# ENZANKI.net
KiCad netlist of a schematic drawn in EAGLE
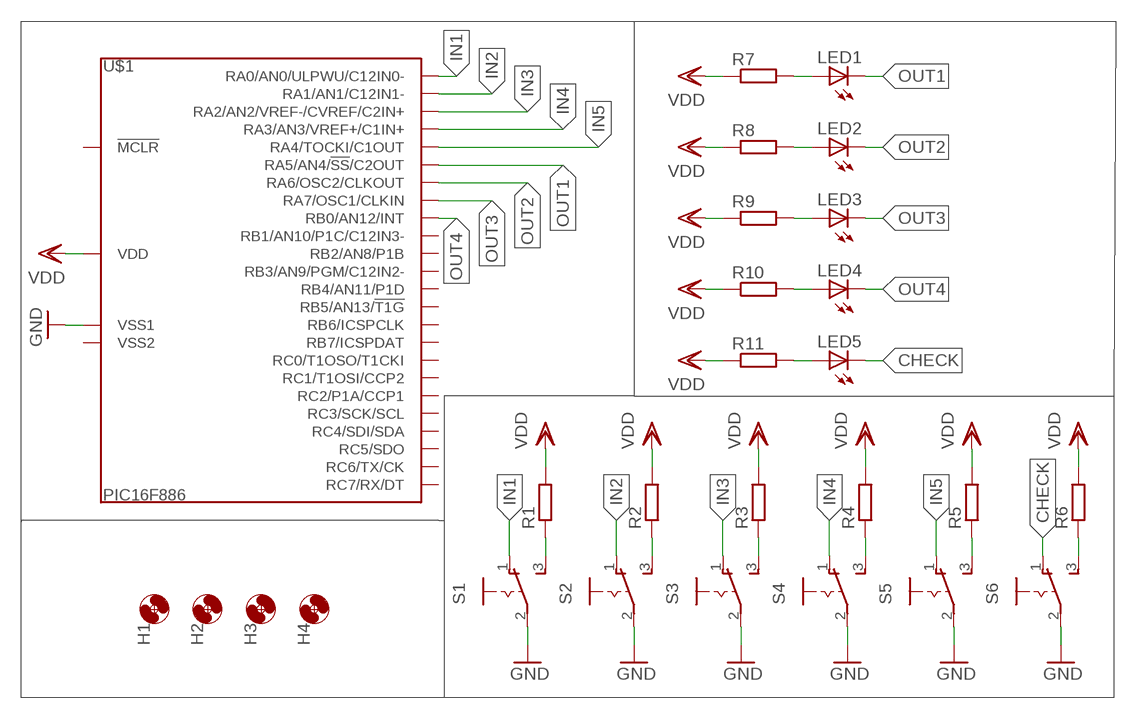
[diagram p0: schematic, sheet 1]

(export (version "E")
  (design (tool "Eeschema 10.0.6"))
  (components
    (comp (ref "H1")
      (value "HOLE3.3M3BOLT")
      (footprint "eagle-import:HOLE3.3")
      (libsource (lib "eagle-import") (part "HOLE3.3M3BOLT"))
    )
    (comp (ref "H2")
      (value "HOLE3.3M3BOLT")
      (footprint "eagle-import:HOLE3.3")
      (libsource (lib "eagle-import") (part "HOLE3.3M3BOLT"))
    )
    (comp (ref "H3")
      (value "HOLE3.3M3BOLT")
      (footprint "eagle-import:HOLE3.3")
      (libsource (lib "eagle-import") (part "HOLE3.3M3BOLT"))
    )
    (comp (ref "H4")
      (value "HOLE3.3M3BOLT")
      (footprint "eagle-import:HOLE3.3")
      (libsource (lib "eagle-import") (part "HOLE3.3M3BOLT"))
    )
    (comp (ref "LED1")
      (value "LED5MM")
      (footprint "eagle-import:LED5MM")
      (libsource (lib "eagle-import") (part "LED5MM"))
    )
    (comp (ref "LED2")
      (value "LED5MM")
      (footprint "eagle-import:LED5MM")
      (libsource (lib "eagle-import") (part "LED5MM"))
    )
    (comp (ref "LED3")
      (value "LED5MM")
      (footprint "eagle-import:LED5MM")
      (libsource (lib "eagle-import") (part "LED5MM"))
    )
    (comp (ref "LED4")
      (value "LED5MM")
      (footprint "eagle-import:LED5MM")
      (libsource (lib "eagle-import") (part "LED5MM"))
    )
    (comp (ref "LED5")
      (value "LED5MM")
      (footprint "eagle-import:LED5MM")
      (libsource (lib "eagle-import") (part "LED5MM"))
    )
    (comp (ref "R1")
      (value "R-EU_R3216W")
      (footprint "eagle-import:R3216W")
      (libsource (lib "eagle-import") (part "R-EU_R3216W"))
    )
    (comp (ref "R2")
      (value "R-EU_R3216W")
      (footprint "eagle-import:R3216W")
      (libsource (lib "eagle-import") (part "R-EU_R3216W"))
    )
    (comp (ref "R3")
      (value "R-EU_R3216W")
      (footprint "eagle-import:R3216W")
      (libsource (lib "eagle-import") (part "R-EU_R3216W"))
    )
    (comp (ref "R4")
      (value "R-EU_R3216W")
      (footprint "eagle-import:R3216W")
      (libsource (lib "eagle-import") (part "R-EU_R3216W"))
    )
    (comp (ref "R5")
      (value "R-EU_R3216W")
      (footprint "eagle-import:R3216W")
      (libsource (lib "eagle-import") (part "R-EU_R3216W"))
    )
    (comp (ref "R6")
      (value "R-EU_R3216W")
      (footprint "eagle-import:R3216W")
      (libsource (lib "eagle-import") (part "R-EU_R3216W"))
    )
    (comp (ref "R7")
      (value "R-EU_R3216W")
      (footprint "eagle-import:R3216W")
      (libsource (lib "eagle-import") (part "R-EU_R3216W"))
    )
    (comp (ref "R8")
      (value "R-EU_R3216W")
      (footprint "eagle-import:R3216W")
      (libsource (lib "eagle-import") (part "R-EU_R3216W"))
    )
    (comp (ref "R9")
      (value "R-EU_R3216W")
      (footprint "eagle-import:R3216W")
      (libsource (lib "eagle-import") (part "R-EU_R3216W"))
    )
    (comp (ref "R10")
      (value "R-EU_R3216W")
      (footprint "eagle-import:R3216W")
      (libsource (lib "eagle-import") (part "R-EU_R3216W"))
    )
    (comp (ref "R11")
      (value "R-EU_R3216W")
      (footprint "eagle-import:R3216W")
      (libsource (lib "eagle-import") (part "R-EU_R3216W"))
    )
    (comp (ref "S1")
      (value "SLIDESW")
      (footprint "eagle-import:SLIDESW")
      (libsource (lib "eagle-import") (part "SLIDESW"))
    )
    (comp (ref "S2")
      (value "SLIDESW")
      (footprint "eagle-import:SLIDESW")
      (libsource (lib "eagle-import") (part "SLIDESW"))
    )
    (comp (ref "S3")
      (value "SLIDESW")
      (footprint "eagle-import:SLIDESW")
      (libsource (lib "eagle-import") (part "SLIDESW"))
    )
    (comp (ref "S4")
      (value "SLIDESW")
      (footprint "eagle-import:SLIDESW")
      (libsource (lib "eagle-import") (part "SLIDESW"))
    )
    (comp (ref "S5")
      (value "SLIDESW")
      (footprint "eagle-import:SLIDESW")
      (libsource (lib "eagle-import") (part "SLIDESW"))
    )
    (comp (ref "S6")
      (value "SLIDESW")
      (footprint "eagle-import:SLIDESW")
      (libsource (lib "eagle-import") (part "SLIDESW"))
    )
    (comp (ref "U$1")
      (value "PIC16F886")
      (footprint "eagle-import:DIL28")
      (libsource (lib "eagle-import") (part "PIC16F886"))
    )
  )
  (nets
    (net (code "1") (name "CHECK") (class "Default")
      (node (ref "LED5") (pin "K") (pinfunction "C_K") (pintype "passive"))
      (node (ref "S6") (pin "1") (pinfunction "1_1") (pintype "passive"))
    )
    (net (code "2") (name "GND") (class "Default")
      (node (ref "S1") (pin "2") (pinfunction "2_2") (pintype "passive"))
      (node (ref "S2") (pin "2") (pinfunction "2_2") (pintype "passive"))
      (node (ref "S3") (pin "2") (pinfunction "2_2") (pintype "passive"))
      (node (ref "S4") (pin "2") (pinfunction "2_2") (pintype "passive"))
      (node (ref "S5") (pin "2") (pinfunction "2_2") (pintype "passive"))
      (node (ref "S6") (pin "2") (pinfunction "2_2") (pintype "passive"))
      (node (ref "U$1") (pin "8") (pinfunction "VSS1_8") (pintype "passive"))
    )
    (net (code "3") (name "IN1") (class "Default")
      (node (ref "S1") (pin "1") (pinfunction "1_1") (pintype "passive"))
      (node (ref "U$1") (pin "2") (pinfunction "RA0/AN0/ULPWU/C12IN0-_2") (pintype "passive"))
    )
    (net (code "4") (name "IN2") (class "Default")
      (node (ref "S2") (pin "1") (pinfunction "1_1") (pintype "passive"))
      (node (ref "U$1") (pin "3") (pinfunction "RA1/AN1/C12IN1-_3") (pintype "passive"))
    )
    (net (code "5") (name "IN3") (class "Default")
      (node (ref "S3") (pin "1") (pinfunction "1_1") (pintype "passive"))
      (node (ref "U$1") (pin "4") (pinfunction "RA2/AN2/VREF-/CVREF/C2IN+_4") (pintype "passive"))
    )
    (net (code "6") (name "IN4") (class "Default")
      (node (ref "S4") (pin "1") (pinfunction "1_1") (pintype "passive"))
      (node (ref "U$1") (pin "5") (pinfunction "RA3/AN3/VREF+/C1IN+_5") (pintype "passive"))
    )
    (net (code "7") (name "IN5") (class "Default")
      (node (ref "S5") (pin "1") (pinfunction "1_1") (pintype "passive"))
      (node (ref "U$1") (pin "6") (pinfunction "RA4/TOCKI/C1OUT_6") (pintype "passive"))
    )
    (net (code "8") (name "Net-(LED1-PadA)") (class "Default")
      (node (ref "LED1") (pin "A") (pinfunction "A_A") (pintype "passive"))
      (node (ref "R7") (pin "2") (pinfunction "2_2") (pintype "passive"))
    )
    (net (code "9") (name "Net-(LED2-PadA)") (class "Default")
      (node (ref "LED2") (pin "A") (pinfunction "A_A") (pintype "passive"))
      (node (ref "R8") (pin "2") (pinfunction "2_2") (pintype "passive"))
    )
    (net (code "10") (name "Net-(LED3-PadA)") (class "Default")
      (node (ref "LED3") (pin "A") (pinfunction "A_A") (pintype "passive"))
      (node (ref "R9") (pin "2") (pinfunction "2_2") (pintype "passive"))
    )
    (net (code "11") (name "Net-(LED4-PadA)") (class "Default")
      (node (ref "LED4") (pin "A") (pinfunction "A_A") (pintype "passive"))
      (node (ref "R10") (pin "2") (pinfunction "2_2") (pintype "passive"))
    )
    (net (code "12") (name "Net-(LED5-PadA)") (class "Default")
      (node (ref "LED5") (pin "A") (pinfunction "A_A") (pintype "passive"))
      (node (ref "R11") (pin "2") (pinfunction "2_2") (pintype "passive"))
    )
    (net (code "13") (name "Net-(R1-Pad1)") (class "Default")
      (node (ref "R1") (pin "1") (pinfunction "1_1") (pintype "passive"))
      (node (ref "S1") (pin "3") (pinfunction "3_3") (pintype "passive"))
    )
    (net (code "14") (name "Net-(R2-Pad1)") (class "Default")
      (node (ref "R2") (pin "1") (pinfunction "1_1") (pintype "passive"))
      (node (ref "S2") (pin "3") (pinfunction "3_3") (pintype "passive"))
    )
    (net (code "15") (name "Net-(R3-Pad1)") (class "Default")
      (node (ref "R3") (pin "1") (pinfunction "1_1") (pintype "passive"))
      (node (ref "S3") (pin "3") (pinfunction "3_3") (pintype "passive"))
    )
    (net (code "16") (name "Net-(R4-Pad1)") (class "Default")
      (node (ref "R4") (pin "1") (pinfunction "1_1") (pintype "passive"))
      (node (ref "S4") (pin "3") (pinfunction "3_3") (pintype "passive"))
    )
    (net (code "17") (name "Net-(R5-Pad1)") (class "Default")
      (node (ref "R5") (pin "1") (pinfunction "1_1") (pintype "passive"))
      (node (ref "S5") (pin "3") (pinfunction "3_3") (pintype "passive"))
    )
    (net (code "18") (name "Net-(R6-Pad1)") (class "Default")
      (node (ref "R6") (pin "1") (pinfunction "1_1") (pintype "passive"))
      (node (ref "S6") (pin "3") (pinfunction "3_3") (pintype "passive"))
    )
    (net (code "19") (name "OUT1") (class "Default")
      (node (ref "LED1") (pin "K") (pinfunction "C_K") (pintype "passive"))
      (node (ref "U$1") (pin "7") (pinfunction "RA5/AN4/~{SS}/C2OUT_7") (pintype "passive"))
    )
    (net (code "20") (name "OUT2") (class "Default")
      (node (ref "LED2") (pin "K") (pinfunction "C_K") (pintype "passive"))
      (node (ref "U$1") (pin "10") (pinfunction "RA6/OSC2/CLKOUT_10") (pintype "passive"))
    )
    (net (code "21") (name "OUT3") (class "Default")
      (node (ref "LED3") (pin "K") (pinfunction "C_K") (pintype "passive"))
      (node (ref "U$1") (pin "9") (pinfunction "RA7/OSC1/CLKIN_9") (pintype "passive"))
    )
    (net (code "22") (name "OUT4") (class "Default")
      (node (ref "LED4") (pin "K") (pinfunction "C_K") (pintype "passive"))
      (node (ref "U$1") (pin "21") (pinfunction "RB0/AN12/INT_21") (pintype "passive"))
    )
    (net (code "23") (name "VDD") (class "Default")
      (node (ref "R1") (pin "2") (pinfunction "2_2") (pintype "passive"))
      (node (ref "R10") (pin "1") (pinfunction "1_1") (pintype "passive"))
      (node (ref "R11") (pin "1") (pinfunction "1_1") (pintype "passive"))
      (node (ref "R2") (pin "2") (pinfunction "2_2") (pintype "passive"))
      (node (ref "R3") (pin "2") (pinfunction "2_2") (pintype "passive"))
      (node (ref "R4") (pin "2") (pinfunction "2_2") (pintype "passive"))
      (node (ref "R5") (pin "2") (pinfunction "2_2") (pintype "passive"))
      (node (ref "R6") (pin "2") (pinfunction "2_2") (pintype "passive"))
      (node (ref "R7") (pin "1") (pinfunction "1_1") (pintype "passive"))
      (node (ref "R8") (pin "1") (pinfunction "1_1") (pintype "passive"))
      (node (ref "R9") (pin "1") (pinfunction "1_1") (pintype "passive"))
      (node (ref "U$1") (pin "20") (pinfunction "VDD_20") (pintype "passive"))
    )
    (net (code "24") (name "unconnected-(U$1-RB1{slash}AN10{slash}P1C{slash}C12IN3--Pad22)") (class "Default")
      (node (ref "U$1") (pin "22") (pinfunction "RB1/AN10/P1C/C12IN3-_22") (pintype "passive"))
    )
    (net (code "25") (name "unconnected-(U$1-RB2{slash}AN8{slash}P1B-Pad23)") (class "Default")
      (node (ref "U$1") (pin "23") (pinfunction "RB2/AN8/P1B_23") (pintype "passive"))
    )
    (net (code "26") (name "unconnected-(U$1-RB3{slash}AN9{slash}PGM{slash}C12IN2--Pad24)") (class "Default")
      (node (ref "U$1") (pin "24") (pinfunction "RB3/AN9/PGM/C12IN2-_24") (pintype "passive"))
    )
    (net (code "27") (name "unconnected-(U$1-RB4{slash}AN11{slash}P1D-Pad25)") (class "Default")
      (node (ref "U$1") (pin "25") (pinfunction "RB4/AN11/P1D_25") (pintype "passive"))
    )
    (net (code "28") (name "unconnected-(U$1-RB5{slash}AN13{slash}~{T1G}-Pad26)") (class "Default")
      (node (ref "U$1") (pin "26") (pinfunction "RB5/AN13/~{T1G}_26") (pintype "passive"))
    )
    (net (code "29") (name "unconnected-(U$1-RB6{slash}ICSPCLK-Pad27)") (class "Default")
      (node (ref "U$1") (pin "27") (pinfunction "RB6/ICSPCLK_27") (pintype "passive"))
    )
    (net (code "30") (name "unconnected-(U$1-RB7{slash}ICSPDAT-Pad28)") (class "Default")
      (node (ref "U$1") (pin "28") (pinfunction "RB7/ICSPDAT_28") (pintype "passive"))
    )
    (net (code "31") (name "unconnected-(U$1-RC0{slash}T1OSO{slash}T1CKI-Pad11)") (class "Default")
      (node (ref "U$1") (pin "11") (pinfunction "RC0/T1OSO/T1CKI_11") (pintype "passive"))
    )
    (net (code "32") (name "unconnected-(U$1-RC1{slash}T1OSI{slash}CCP2-Pad12)") (class "Default")
      (node (ref "U$1") (pin "12") (pinfunction "RC1/T1OSI/CCP2_12") (pintype "passive"))
    )
    (net (code "33") (name "unconnected-(U$1-RC2{slash}P1A{slash}CCP1-Pad13)") (class "Default")
      (node (ref "U$1") (pin "13") (pinfunction "RC2/P1A/CCP1_13") (pintype "passive"))
    )
    (net (code "34") (name "unconnected-(U$1-RC3{slash}SCK{slash}SCL-Pad14)") (class "Default")
      (node (ref "U$1") (pin "14") (pinfunction "RC3/SCK/SCL_14") (pintype "passive"))
    )
    (net (code "35") (name "unconnected-(U$1-RC4{slash}SDI{slash}SDA-Pad15)") (class "Default")
      (node (ref "U$1") (pin "15") (pinfunction "RC4/SDI/SDA_15") (pintype "passive"))
    )
    (net (code "36") (name "unconnected-(U$1-RC5{slash}SDO-Pad16)") (class "Default")
      (node (ref "U$1") (pin "16") (pinfunction "RC5/SDO_16") (pintype "passive"))
    )
    (net (code "37") (name "unconnected-(U$1-RC6{slash}TX{slash}CK-Pad17)") (class "Default")
      (node (ref "U$1") (pin "17") (pinfunction "RC6/TX/CK_17") (pintype "passive"))
    )
    (net (code "38") (name "unconnected-(U$1-RC7{slash}RX{slash}DT-Pad18)") (class "Default")
      (node (ref "U$1") (pin "18") (pinfunction "RC7/RX/DT_18") (pintype "passive"))
    )
    (net (code "39") (name "unconnected-(U$1-VSS2-Pad19)") (class "Default")
      (node (ref "U$1") (pin "19") (pinfunction "VSS2_19") (pintype "passive"))
    )
    (net (code "40") (name "unconnected-(U$1-~{MCLR}-Pad1)") (class "Default")
      (node (ref "U$1") (pin "1") (pinfunction "~{MCLR}_1") (pintype "passive"))
    )
  )
)
